# main.net
KiCad netlist of a schematic drawn in EAGLE
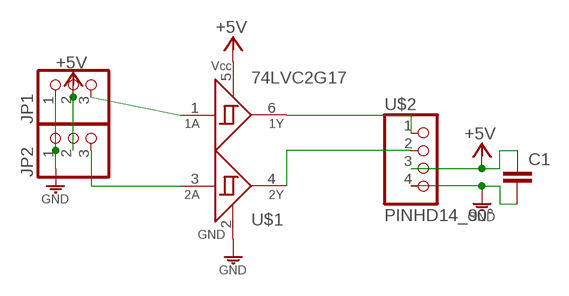
[diagram p0: schematic, sheet 1]

(export (version "E")
  (design (tool "Eeschema 10.0.6"))
  (components
    (comp (ref "C1")
      (value "MLCC-2")
      (footprint "eagle-import:MLCC_25")
      (libsource (lib "eagle-import") (part "MLCC-2"))
    )
    (comp (ref "JP1")
      (value "PINHD-13_90°")
      (footprint "eagle-import:1_3_90")
      (libsource (lib "eagle-import") (part "PINHD-13_90°"))
    )
    (comp (ref "JP2")
      (value "PINHD-13_90°")
      (footprint "eagle-import:1_3_90")
      (libsource (lib "eagle-import") (part "PINHD-13_90°"))
    )
    (comp (ref "U$1")
      (value "74LVC2G17")
      (footprint "eagle-import:74LVC2G17")
      (libsource (lib "eagle-import") (part "74LVC2G17"))
    )
    (comp (ref "U$2")
      (value "PINHD14_90°")
      (footprint "eagle-import:1_4_90")
      (libsource (lib "eagle-import") (part "PINHD14_90°"))
    )
  )
  (nets
    (net (code "1") (name "+5V") (class "Default")
      (node (ref "C1") (pin "1") (pinfunction "1_1") (pintype "passive"))
      (node (ref "JP1") (pin "2") (pinfunction "2_2") (pintype "passive"))
      (node (ref "JP2") (pin "2") (pinfunction "2_2") (pintype "passive"))
      (node (ref "U$1") (pin "5") (pinfunction "5_5") (pintype "bidirectional"))
      (node (ref "U$2") (pin "3") (pinfunction "3_3") (pintype "passive"))
    )
    (net (code "2") (name "GND") (class "Default")
      (node (ref "C1") (pin "2") (pinfunction "2_2") (pintype "passive"))
      (node (ref "JP1") (pin "1") (pinfunction "1_1") (pintype "passive"))
      (node (ref "JP2") (pin "1") (pinfunction "1_1") (pintype "passive"))
      (node (ref "U$1") (pin "2") (pinfunction "2_2") (pintype "bidirectional"))
      (node (ref "U$2") (pin "4") (pinfunction "4_4") (pintype "passive"))
    )
    (net (code "3") (name "Net-(JP1-Pad3)") (class "Default")
      (node (ref "JP1") (pin "3") (pinfunction "3_3") (pintype "passive"))
      (node (ref "U$1") (pin "1") (pinfunction "1_1") (pintype "bidirectional"))
    )
    (net (code "4") (name "Net-(JP2-Pad3)") (class "Default")
      (node (ref "JP2") (pin "3") (pinfunction "3_3") (pintype "passive"))
      (node (ref "U$1") (pin "3") (pinfunction "3_3") (pintype "bidirectional"))
    )
    (net (code "5") (name "Net-(U$1-Pad4)") (class "Default")
      (node (ref "U$1") (pin "4") (pinfunction "4_4") (pintype "bidirectional"))
      (node (ref "U$2") (pin "2") (pinfunction "2_2") (pintype "passive"))
    )
    (net (code "6") (name "Net-(U$1-Pad6)") (class "Default")
      (node (ref "U$1") (pin "6") (pinfunction "6_6") (pintype "bidirectional"))
      (node (ref "U$2") (pin "1") (pinfunction "1_1") (pintype "passive"))
    )
  )
)
